# WidgetEsp8266RGBv5StripIR.net
KiCad netlist of a schematic drawn in EAGLE
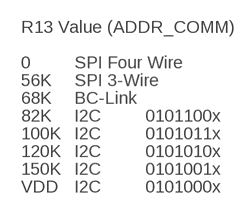
[diagram p0: schematic, sheet 1, part 1 of 3]
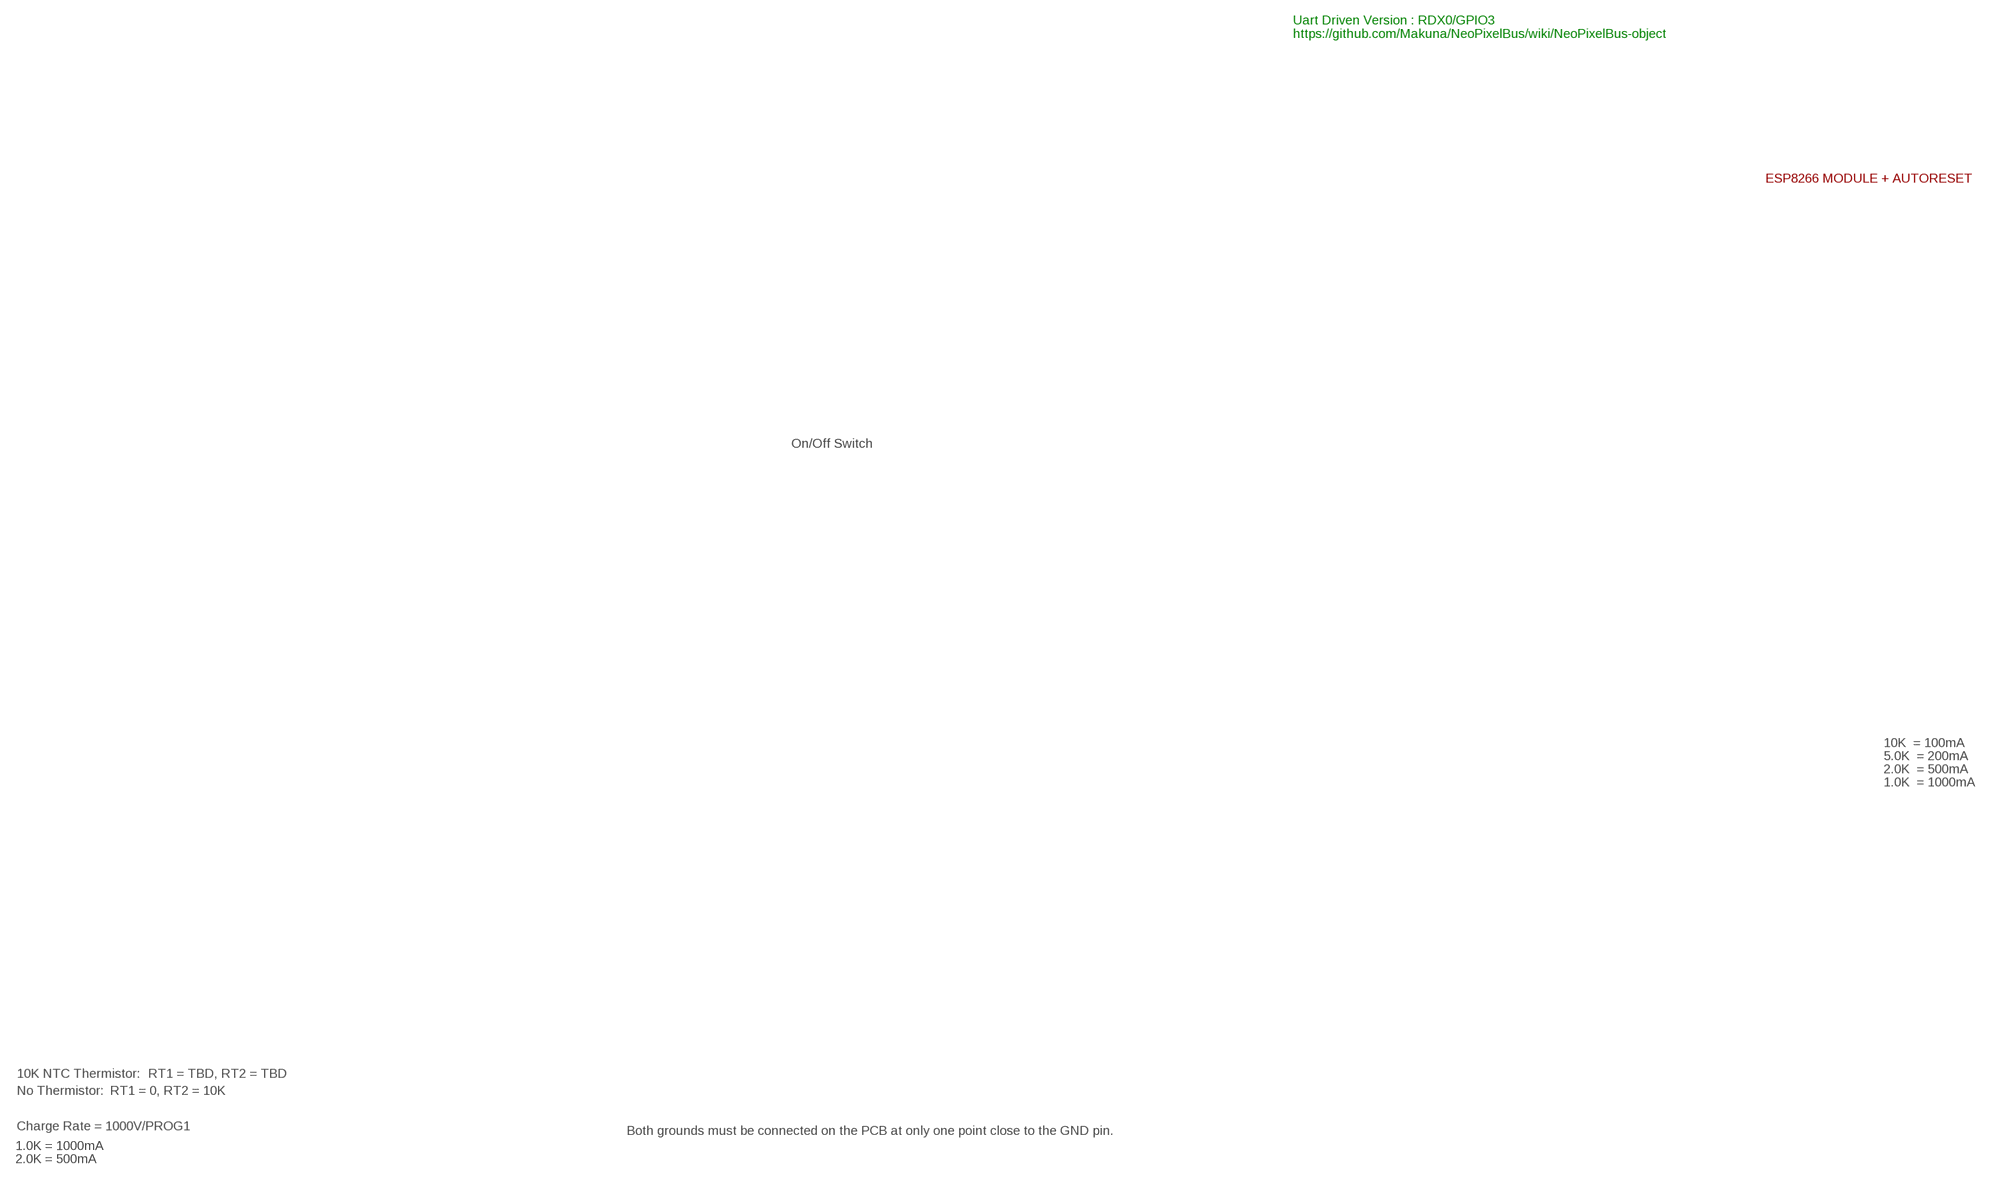
[diagram p1: schematic, sheet 1, part 2 of 3]
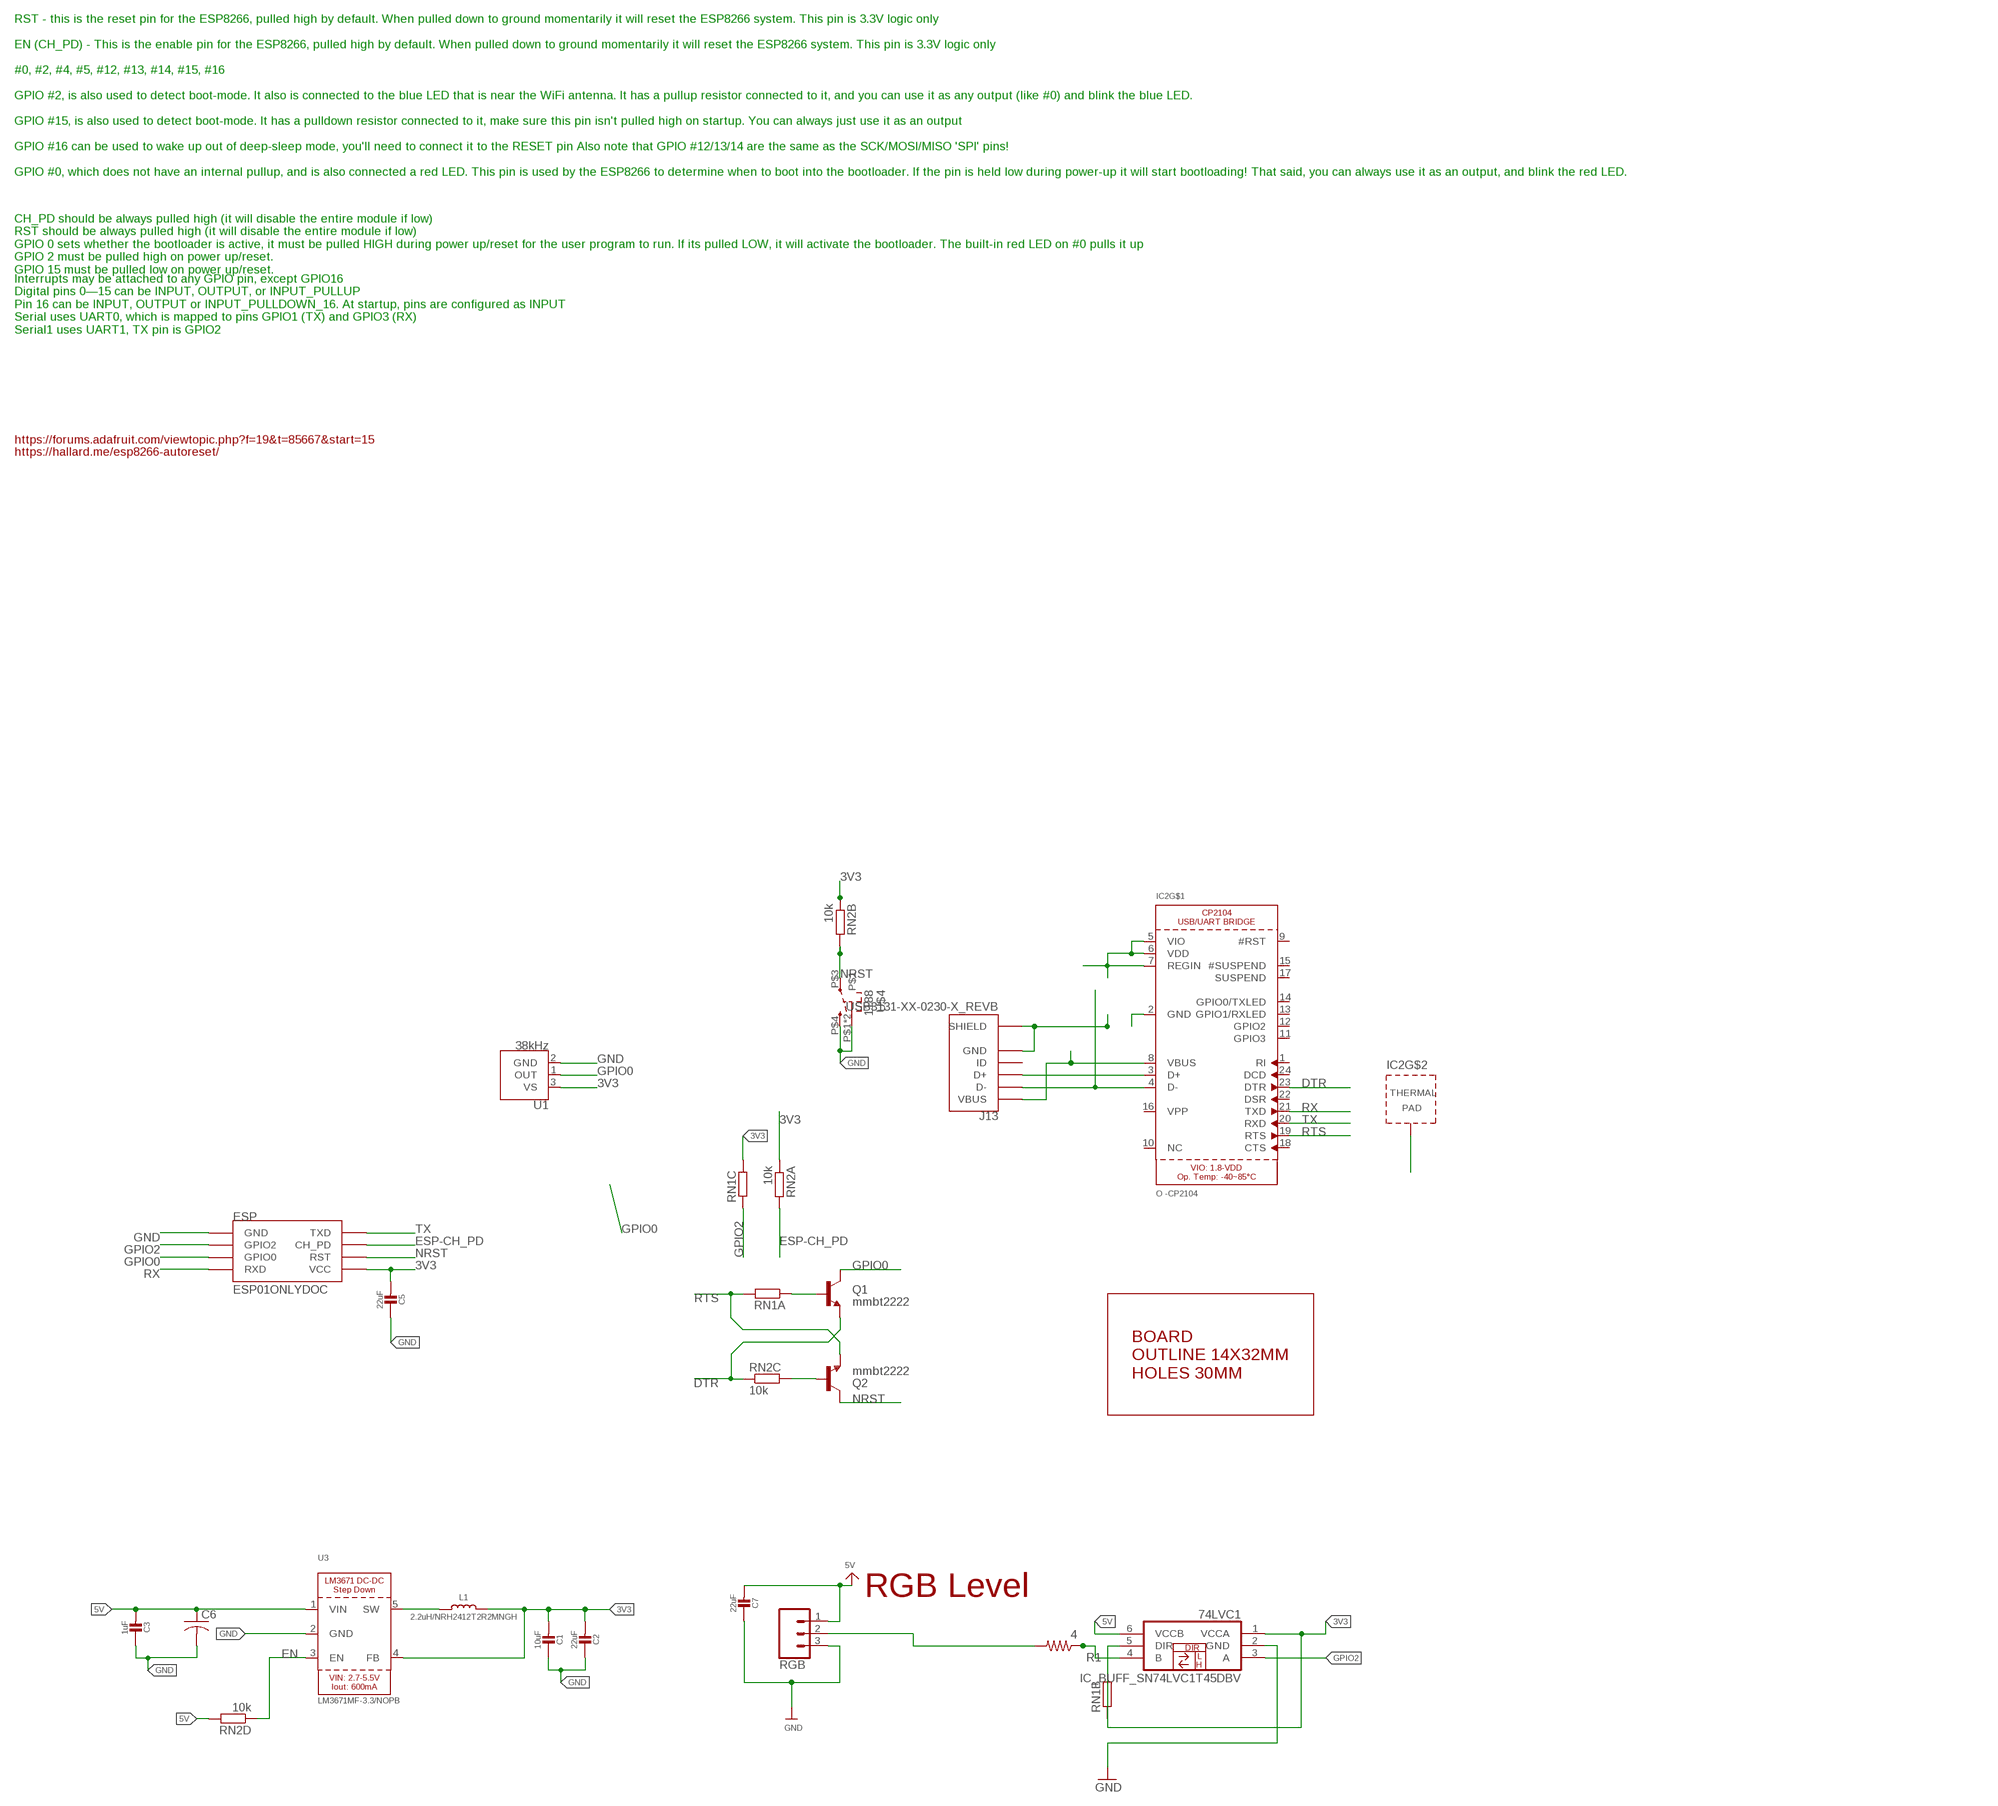
[diagram p2: schematic, sheet 1, part 3 of 3]

(export (version "E")
  (design (tool "Eeschema 10.0.6"))
  (components
    (comp (ref "74LVC1")
      (value "IC_BUFF_SN74LVC1T45DBV")
      (footprint "eagle-import:DBV-R-PDSO-G6")
      (libsource (lib "eagle-import") (part "IC_BUFF_SN74LVC1T45DBV"))
    )
    (comp (ref "C1")
      (value "10uF")
      (footprint "eagle-import:0805-NO")
      (libsource (lib "eagle-import") (part "CAP_CERAMIC0805-NOOUTLINE"))
    )
    (comp (ref "C2")
      (value "22uF")
      (footprint "eagle-import:0805-NO")
      (libsource (lib "eagle-import") (part "CAP_CERAMIC0805-NOOUTLINE"))
    )
    (comp (ref "C3")
      (value "1uF")
      (footprint "eagle-import:0805-NO")
      (libsource (lib "eagle-import") (part "CAP_CERAMIC0805-NOOUTLINE"))
    )
    (comp (ref "C5")
      (value "22uF")
      (footprint "eagle-import:0805-NO")
      (libsource (lib "eagle-import") (part "CAP_CERAMIC0805-NOOUTLINE"))
    )
    (comp (ref "C6")
      (value "C-USC3225")
      (footprint "eagle-import:C3225")
      (libsource (lib "eagle-import") (part "C-USC3225"))
    )
    (comp (ref "C7")
      (value "22uF")
      (footprint "eagle-import:0805-NO")
      (libsource (lib "eagle-import") (part "CAP_CERAMIC0805-NOOUTLINE"))
    )
    (comp (ref "ESP")
      (value "ESP01ONLYDOC")
      (footprint "eagle-import:ESP01-NONOSILK")
      (libsource (lib "eagle-import") (part "ESP01ONLYDOC"))
    )
    (comp (ref "IC2")
      (value "O -CP2104")
      (footprint "eagle-import:QFN24_4MM_SMSC")
      (libsource (lib "eagle-import") (part "CP2104"))
    )
    (comp (ref "J13")
      (value "USB3131-XX-0230-X_REVB")
      (footprint "eagle-import:GCT_USB3131-XX-0230-X_REVB")
      (fields
        (field (name "MF") "Global Connector Technology")
        (field (name "MP") "USB3131-30-0230-A")
        (field (name "SPICEPREFIX") "X")
      )
      (libsource (lib "eagle-import") (part "USB3131-XX-0230-X_REVB"))
    )
    (comp (ref "L1")
      (value "2.2uH/NRH2412T2R2MNGH")
      (footprint "eagle-import:INDUCTOR_TAIYOYUDEN_NRH2412T")
      (libsource (lib "eagle-import") (part "INDUCTORNRH2412T"))
    )
    (comp (ref "Q1")
      (value "mmbt2222")
      (footprint "eagle-import:SOT23-3")
      (libsource (lib "eagle-import") (part "TRANSISTOR_NPNSOT23-3"))
    )
    (comp (ref "Q2")
      (value "mmbt2222")
      (footprint "eagle-import:SOT23-3")
      (libsource (lib "eagle-import") (part "TRANSISTOR_NPNSOT23-3"))
    )
    (comp (ref "R1")
      (value "4")
      (footprint "eagle-import:0805")
      (libsource (lib "eagle-import") (part "RESISTOR0805-RES"))
    )
    (comp (ref "RGB")
      (value "CONN_03LONGPADS")
      (footprint "eagle-import:1X03_LONGPADS")
      (libsource (lib "eagle-import") (part "CONN_03LONGPADS"))
    )
    (comp (ref "RN1")
      (value "RESISTOR_ARRAY_4")
      (footprint "eagle-import:RN8P-4R-CRA06S")
      (libsource (lib "eagle-import") (part "RESISTOR_ARRAY_4"))
    )
    (comp (ref "RN2")
      (value "10k")
      (footprint "eagle-import:RN8P-4R-CRA06S")
      (libsource (lib "eagle-import") (part "RESISTOR_ARRAY_4"))
    )
    (comp (ref "U$4")
      (value "1188")
      (footprint "eagle-import:1188")
      (libsource (lib "eagle-import") (part "1188"))
    )
    (comp (ref "U$7")
      (value "BOARD14X32")
      (footprint "eagle-import:14X32")
      (libsource (lib "eagle-import") (part "BOARD14X32"))
    )
    (comp (ref "U1")
      (value "38kHz")
      (footprint "eagle-import:TSOP382")
      (libsource (lib "eagle-import") (part "TSOP38238"))
    )
    (comp (ref "U3")
      (value "LM3671MF-3.3/NOPB")
      (footprint "eagle-import:SOT23-5")
      (libsource (lib "eagle-import") (part "VREG_LM3671"))
    )
  )
  (nets
    (net (code "1") (name "/DTR") (class "Default")
      (node (ref "IC2") (pin "23") (pinfunction "DTR_23") (pintype "output"))
      (node (ref "Q1") (pin "2") (pinfunction "E_2") (pintype "passive"))
      (node (ref "RN2") (pin "3") (pinfunction "1_3") (pintype "passive"))
    )
    (net (code "2") (name "/EN") (class "Default")
      (node (ref "RN2") (pin "4") (pinfunction "1_4") (pintype "passive"))
      (node (ref "U3") (pin "3") (pinfunction "EN_3") (pintype "input"))
    )
    (net (code "3") (name "/ESP-CH_PD") (class "Default")
      (node (ref "ESP") (pin "CH_PD") (pinfunction "CH_PD_CH_PD") (pintype "bidirectional"))
      (node (ref "RN2") (pin "8") (pinfunction "2_8") (pintype "passive"))
    )
    (net (code "4") (name "/GPIO0") (class "Default")
      (node (ref "ESP") (pin "GPIO0") (pinfunction "GPIO0_GPIO0") (pintype "bidirectional"))
      (node (ref "Q1") (pin "3") (pinfunction "C_3") (pintype "passive"))
      (node (ref "U1") (pin "1") (pinfunction "OUT_1") (pintype "bidirectional"))
    )
    (net (code "5") (name "/NRST") (class "Default")
      (node (ref "ESP") (pin "RST") (pinfunction "RST_RST") (pintype "bidirectional"))
      (node (ref "Q2") (pin "3") (pinfunction "C_3") (pintype "passive"))
      (node (ref "RN2") (pin "7") (pinfunction "2_7") (pintype "passive"))
      (node (ref "U$4") (pin "P$3") (pinfunction "1_P$3") (pintype "passive"))
    )
    (net (code "6") (name "/RTS") (class "Default")
      (node (ref "IC2") (pin "19") (pinfunction "RTS_19") (pintype "output"))
      (node (ref "Q2") (pin "2") (pinfunction "E_2") (pintype "passive"))
      (node (ref "RN1") (pin "8") (pinfunction "2_8") (pintype "passive"))
    )
    (net (code "7") (name "/RX") (class "Default")
      (node (ref "ESP") (pin "RX") (pinfunction "RXD_RX") (pintype "bidirectional"))
      (node (ref "IC2") (pin "21") (pinfunction "TXD_21") (pintype "output"))
    )
    (net (code "8") (name "/TX") (class "Default")
      (node (ref "ESP") (pin "TX") (pinfunction "TXD_TX") (pintype "bidirectional"))
      (node (ref "IC2") (pin "20") (pinfunction "RXD_20") (pintype "input"))
    )
    (net (code "9") (name "3V3") (class "Default")
      (node (ref "74LVC1") (pin "1") (pinfunction "VCCA_1") (pintype "power_in"))
      (node (ref "C1") (pin "2") (pinfunction "2_2") (pintype "passive"))
      (node (ref "C2") (pin "2") (pinfunction "2_2") (pintype "passive"))
      (node (ref "C5") (pin "2") (pinfunction "2_2") (pintype "passive"))
      (node (ref "ESP") (pin "VCC") (pinfunction "VCC_VCC") (pintype "bidirectional"))
      (node (ref "IC2") (pin "5") (pinfunction "VIO_5") (pintype "power_in"))
      (node (ref "IC2") (pin "6") (pinfunction "VDD_6") (pintype "power_in"))
      (node (ref "IC2") (pin "7") (pinfunction "REGIN_7") (pintype "power_in"))
      (node (ref "L1") (pin "2") (pinfunction "2_2") (pintype "passive"))
      (node (ref "RN1") (pin "6") (pinfunction "2_6") (pintype "passive"))
      (node (ref "RN1") (pin "7") (pinfunction "2_7") (pintype "passive"))
      (node (ref "RN2") (pin "1") (pinfunction "1_1") (pintype "passive"))
      (node (ref "RN2") (pin "2") (pinfunction "1_2") (pintype "passive"))
      (node (ref "U1") (pin "3") (pinfunction "VS_3") (pintype "bidirectional"))
      (node (ref "U3") (pin "4") (pinfunction "FB_4") (pintype "power_in"))
    )
    (net (code "10") (name "5V") (class "Default")
      (node (ref "74LVC1") (pin "6") (pinfunction "VCCB_6") (pintype "power_in"))
      (node (ref "C3") (pin "2") (pinfunction "2_2") (pintype "passive"))
      (node (ref "C6") (pin "1") (pinfunction "1_1") (pintype "passive"))
      (node (ref "C7") (pin "2") (pinfunction "2_2") (pintype "passive"))
      (node (ref "IC2") (pin "8") (pinfunction "VBUS_8") (pintype "power_in"))
      (node (ref "J13") (pin "1") (pinfunction "VBUS_1") (pintype "power_in"))
      (node (ref "RGB") (pin "1") (pinfunction "1_1") (pintype "passive"))
      (node (ref "RN2") (pin "5") (pinfunction "2_5") (pintype "passive"))
      (node (ref "U3") (pin "1") (pinfunction "VIN_1") (pintype "power_in"))
    )
    (net (code "11") (name "GND") (class "Default")
      (node (ref "74LVC1") (pin "2") (pinfunction "GND_2") (pintype "power_in"))
      (node (ref "C1") (pin "1") (pinfunction "1_1") (pintype "passive"))
      (node (ref "C2") (pin "1") (pinfunction "1_1") (pintype "passive"))
      (node (ref "C3") (pin "1") (pinfunction "1_1") (pintype "passive"))
      (node (ref "C5") (pin "1") (pinfunction "1_1") (pintype "passive"))
      (node (ref "C6") (pin "2") (pinfunction "2_2") (pintype "passive"))
      (node (ref "C7") (pin "1") (pinfunction "1_1") (pintype "passive"))
      (node (ref "ESP") (pin "GND") (pinfunction "GND_GND") (pintype "bidirectional"))
      (node (ref "IC2") (pin "2") (pinfunction "GND_2") (pintype "power_in"))
      (node (ref "IC2") (pin "THERM") (pinfunction "TP_THERM") (pintype "power_in"))
      (node (ref "J13") (pin "5") (pinfunction "GND_5") (pintype "power_in"))
      (node (ref "J13") (pin "6") (pinfunction "SHIELD_6") (pintype "passive"))
      (node (ref "J13") (pin "7") (pinfunction "SHIELD_7") (pintype "passive"))
      (node (ref "RGB") (pin "3") (pinfunction "3_3") (pintype "passive"))
      (node (ref "U$4") (pin "P$1") (pinfunction "P$1_P$1") (pintype "bidirectional"))
      (node (ref "U$4") (pin "P$2") (pinfunction "P$1_P$2") (pintype "bidirectional"))
      (node (ref "U$4") (pin "P$4") (pinfunction "3_P$4") (pintype "passive"))
      (node (ref "U1") (pin "2") (pinfunction "GND_2") (pintype "bidirectional"))
      (node (ref "U3") (pin "2") (pinfunction "GND_2") (pintype "power_in"))
    )
    (net (code "12") (name "GPIO2") (class "Default")
      (node (ref "74LVC1") (pin "3") (pinfunction "A_3") (pintype "bidirectional"))
      (node (ref "ESP") (pin "GPIO2") (pinfunction "GPIO2_GPIO2") (pintype "bidirectional"))
      (node (ref "RN1") (pin "3") (pinfunction "1_3") (pintype "passive"))
    )
    (net (code "13") (name "Net-(74LVC1-B)") (class "Default")
      (node (ref "74LVC1") (pin "4") (pinfunction "B_4") (pintype "bidirectional"))
      (node (ref "R1") (pin "1") (pinfunction "1_1") (pintype "passive"))
    )
    (net (code "14") (name "Net-(74LVC1-DIR)") (class "Default")
      (node (ref "74LVC1") (pin "5") (pinfunction "DIR_5") (pintype "input"))
      (node (ref "RN1") (pin "2") (pinfunction "1_2") (pintype "passive"))
    )
    (net (code "15") (name "Net-(IC2A-D+)") (class "Default")
      (node (ref "IC2") (pin "3") (pinfunction "D+_3") (pintype "bidirectional"))
      (node (ref "J13") (pin "3") (pinfunction "D+_3") (pintype "bidirectional"))
    )
    (net (code "16") (name "Net-(IC2A-D-)") (class "Default")
      (node (ref "IC2") (pin "4") (pinfunction "D-_4") (pintype "bidirectional"))
      (node (ref "J13") (pin "2") (pinfunction "D-_2") (pintype "bidirectional"))
    )
    (net (code "17") (name "Net-(Q1-B)") (class "Default")
      (node (ref "Q1") (pin "1") (pinfunction "B_1") (pintype "passive"))
      (node (ref "RN1") (pin "1") (pinfunction "1_1") (pintype "passive"))
    )
    (net (code "18") (name "Net-(Q2-B)") (class "Default")
      (node (ref "Q2") (pin "1") (pinfunction "B_1") (pintype "passive"))
      (node (ref "RN2") (pin "6") (pinfunction "2_6") (pintype "passive"))
    )
    (net (code "19") (name "Net-(R1-Pad2)") (class "Default")
      (node (ref "R1") (pin "2") (pinfunction "2_2") (pintype "passive"))
      (node (ref "RGB") (pin "2") (pinfunction "2_2") (pintype "passive"))
    )
    (net (code "20") (name "Net-(U3-SW)") (class "Default")
      (node (ref "L1") (pin "1") (pinfunction "1_1") (pintype "passive"))
      (node (ref "U3") (pin "5") (pinfunction "SW_5") (pintype "output"))
    )
    (net (code "21") (name "unconnected-(IC2A-#RST-Pad9)") (class "Default")
      (node (ref "IC2") (pin "9") (pinfunction "#RST_9") (pintype "bidirectional"))
    )
    (net (code "22") (name "unconnected-(IC2A-#SUSPEND-Pad15)") (class "Default")
      (node (ref "IC2") (pin "15") (pinfunction "#SUSPEND_15") (pintype "output"))
    )
    (net (code "23") (name "unconnected-(IC2A-CTS-Pad18)") (class "Default")
      (node (ref "IC2") (pin "18") (pinfunction "CTS_18") (pintype "input"))
    )
    (net (code "24") (name "unconnected-(IC2A-DCD-Pad24)") (class "Default")
      (node (ref "IC2") (pin "24") (pinfunction "DCD_24") (pintype "input"))
    )
    (net (code "25") (name "unconnected-(IC2A-DSR-Pad22)") (class "Default")
      (node (ref "IC2") (pin "22") (pinfunction "DSR_22") (pintype "input"))
    )
    (net (code "26") (name "unconnected-(IC2A-GPIO0{slash}TXLED-Pad14)") (class "Default")
      (node (ref "IC2") (pin "14") (pinfunction "GPIO0/TXLED_14") (pintype "bidirectional"))
    )
    (net (code "27") (name "unconnected-(IC2A-GPIO1{slash}RXLED-Pad13)") (class "Default")
      (node (ref "IC2") (pin "13") (pinfunction "GPIO1/RXLED_13") (pintype "bidirectional"))
    )
    (net (code "28") (name "unconnected-(IC2A-GPIO2-Pad12)") (class "Default")
      (node (ref "IC2") (pin "12") (pinfunction "GPIO2_12") (pintype "bidirectional"))
    )
    (net (code "29") (name "unconnected-(IC2A-GPIO3-Pad11)") (class "Default")
      (node (ref "IC2") (pin "11") (pinfunction "GPIO3_11") (pintype "bidirectional"))
    )
    (net (code "30") (name "unconnected-(IC2A-NC-Pad10)") (class "Default")
      (node (ref "IC2") (pin "10") (pinfunction "NC_10") (pintype "no_connect"))
    )
    (net (code "31") (name "unconnected-(IC2A-RI-Pad1)") (class "Default")
      (node (ref "IC2") (pin "1") (pinfunction "RI_1") (pintype "input"))
    )
    (net (code "32") (name "unconnected-(IC2A-SUSPEND-Pad17)") (class "Default")
      (node (ref "IC2") (pin "17") (pinfunction "SUSPEND_17") (pintype "output"))
    )
    (net (code "33") (name "unconnected-(IC2A-VPP-Pad16)") (class "Default")
      (node (ref "IC2") (pin "16") (pinfunction "VPP_16") (pintype "bidirectional"))
    )
    (net (code "34") (name "unconnected-(J13-ID-Pad4)") (class "Default")
      (node (ref "J13") (pin "4") (pinfunction "ID_4") (pintype "passive"))
    )
  )
)
